# Touchcsreen_PCB.net
KiCad netlist of a schematic drawn in Altium Designer
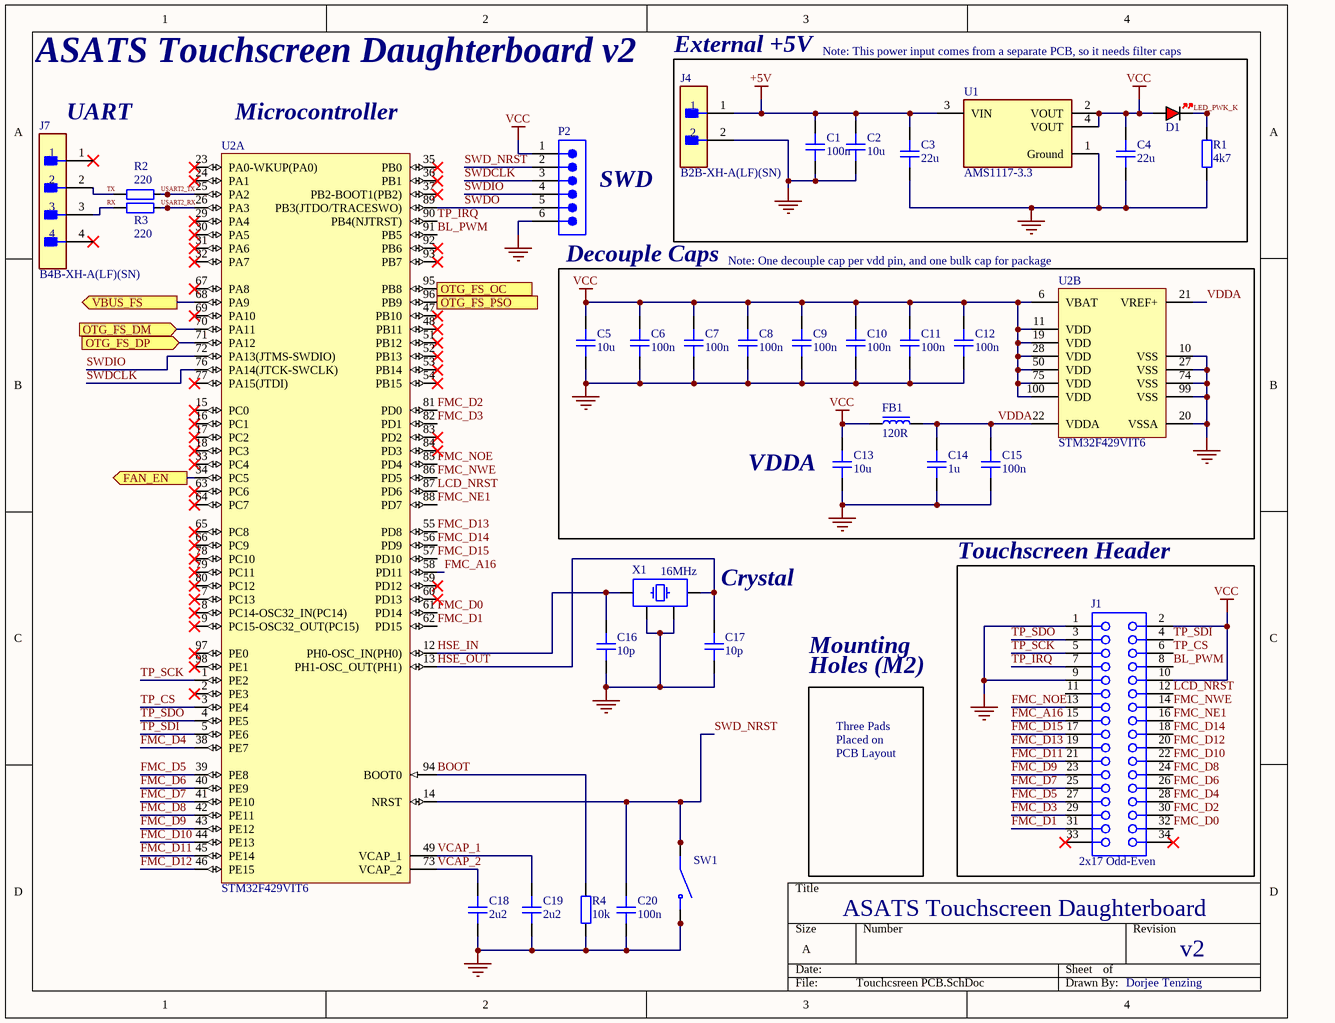
[diagram p0: Touchcsreen PCB.SchDoc]

(export (version "E")
  (design (tool "Eeschema 10.0.6"))
  (components
    (comp (ref "C1")
      (value "100n")
      (footprint "CAP_0402")
      (description "Capacitor SMD 0402")
      (fields
        (field (name "MANUFACTURER") "Samsung Electro-Mechanics")
        (field (name "MANUFACTURER PART NUMBER") "CL05B104KO5NNNC")
      )
      (libsource (lib "Schematic-Lib-PhilsLab") (part "CAP_0402"))
    )
    (comp (ref "C2")
      (value "10u")
      (footprint "CAP_0603")
      (description "Capacitor SMD 0603")
      (fields
        (field (name "MANUFACTURER") "*Samsung Electro-Mechanics")
        (field (name "MANUFACTURER PART NUMBER") "CL10A106MA8NRNC")
      )
      (libsource (lib "Schematic-Lib-PhilsLab") (part "CAP_0603"))
    )
    (comp (ref "C3")
      (value "22u")
      (footprint "CAP_0805")
      (description "Capacitor SMD 0805")
      (fields
        (field (name "MANUFACTURER") "Samsung Electro-Mechanics")
        (field (name "MANUFACTURER PART NUMBER") "CL21A226MAQNNNE")
      )
      (libsource (lib "Schematic-Lib-PhilsLab") (part "CAP_0805"))
    )
    (comp (ref "C4")
      (value "22u")
      (footprint "CAP_0805")
      (description "Capacitor SMD 0805")
      (fields
        (field (name "MANUFACTURER") "Samsung Electro-Mechanics")
        (field (name "MANUFACTURER PART NUMBER") "CL21A226MAQNNNE")
      )
      (libsource (lib "Schematic-Lib-PhilsLab") (part "CAP_0805"))
    )
    (comp (ref "C5")
      (value "10u")
      (footprint "CAP_0603")
      (description "Capacitor SMD 0603")
      (fields
        (field (name "MANUFACTURER") "*Samsung Electro-Mechanics")
        (field (name "MANUFACTURER PART NUMBER") "CL10A106MA8NRNC")
      )
      (libsource (lib "Schematic-Lib-PhilsLab") (part "CAP_0603"))
    )
    (comp (ref "C6")
      (value "100n")
      (footprint "CAP_0402")
      (description "Capacitor SMD 0402")
      (fields
        (field (name "MANUFACTURER") "Samsung Electro-Mechanics")
        (field (name "MANUFACTURER PART NUMBER") "CL05B104KO5NNNC")
      )
      (libsource (lib "Schematic-Lib-PhilsLab") (part "CAP_0402"))
    )
    (comp (ref "C7")
      (value "100n")
      (footprint "CAP_0402")
      (description "Capacitor SMD 0402")
      (fields
        (field (name "MANUFACTURER") "Samsung Electro-Mechanics")
        (field (name "MANUFACTURER PART NUMBER") "CL05B104KO5NNNC")
      )
      (libsource (lib "Schematic-Lib-PhilsLab") (part "CAP_0402"))
    )
    (comp (ref "C8")
      (value "100n")
      (footprint "CAP_0402")
      (description "Capacitor SMD 0402")
      (fields
        (field (name "MANUFACTURER") "Samsung Electro-Mechanics")
        (field (name "MANUFACTURER PART NUMBER") "CL05B104KO5NNNC")
      )
      (libsource (lib "Schematic-Lib-PhilsLab") (part "CAP_0402"))
    )
    (comp (ref "C9")
      (value "100n")
      (footprint "CAP_0402")
      (description "Capacitor SMD 0402")
      (fields
        (field (name "MANUFACTURER") "Samsung Electro-Mechanics")
        (field (name "MANUFACTURER PART NUMBER") "CL05B104KO5NNNC")
      )
      (libsource (lib "Schematic-Lib-PhilsLab") (part "CAP_0402"))
    )
    (comp (ref "C10")
      (value "100n")
      (footprint "CAP_0402")
      (description "Capacitor SMD 0402")
      (fields
        (field (name "MANUFACTURER") "Samsung Electro-Mechanics")
        (field (name "MANUFACTURER PART NUMBER") "CL05B104KO5NNNC")
      )
      (libsource (lib "Schematic-Lib-PhilsLab") (part "CAP_0402"))
    )
    (comp (ref "C11")
      (value "100n")
      (footprint "CAP_0402")
      (description "Capacitor SMD 0402")
      (fields
        (field (name "MANUFACTURER") "Samsung Electro-Mechanics")
        (field (name "MANUFACTURER PART NUMBER") "CL05B104KO5NNNC")
      )
      (libsource (lib "Schematic-Lib-PhilsLab") (part "CAP_0402"))
    )
    (comp (ref "C12")
      (value "100n")
      (footprint "CAP_0402")
      (description "Capacitor SMD 0402")
      (fields
        (field (name "MANUFACTURER") "Samsung Electro-Mechanics")
        (field (name "MANUFACTURER PART NUMBER") "CL05B104KO5NNNC")
      )
      (libsource (lib "Schematic-Lib-PhilsLab") (part "CAP_0402"))
    )
    (comp (ref "C13")
      (value "10u")
      (footprint "CAP_0603")
      (description "Capacitor SMD 0603")
      (fields
        (field (name "MANUFACTURER") "*Samsung Electro-Mechanics")
        (field (name "MANUFACTURER PART NUMBER") "CL10A106MA8NRNC")
      )
      (libsource (lib "Schematic-Lib-PhilsLab") (part "CAP_0603"))
    )
    (comp (ref "C14")
      (value "1u")
      (footprint "CAP_0402")
      (description "Capacitor SMD 0402")
      (fields
        (field (name "MANUFACTURER") "Samsung Electro-Mechanics")
        (field (name "MANUFACTURER PART NUMBER") "CL05A105KA5NQNC")
      )
      (libsource (lib "Schematic-Lib-PhilsLab") (part "CAP_0402"))
    )
    (comp (ref "C15")
      (value "100n")
      (footprint "CAP_0402")
      (description "Capacitor SMD 0402")
      (fields
        (field (name "MANUFACTURER") "Samsung Electro-Mechanics")
        (field (name "MANUFACTURER PART NUMBER") "CL05B104KO5NNNC")
      )
      (libsource (lib "Schematic-Lib-PhilsLab") (part "CAP_0402"))
    )
    (comp (ref "C16")
      (value "10p")
      (footprint "CAP_0402")
      (description "Capacitor SMD 0402")
      (fields
        (field (name "MANUFACTURER") "Samsung Electro-Mechanics")
        (field (name "MANUFACTURER PART NUMBER") "CL05C100JB5NNNC")
      )
      (libsource (lib "Schematic-Lib-PhilsLab") (part "CAP_0402"))
    )
    (comp (ref "C17")
      (value "10p")
      (footprint "CAP_0402")
      (description "Capacitor SMD 0402")
      (fields
        (field (name "MANUFACTURER") "Samsung Electro-Mechanics")
        (field (name "MANUFACTURER PART NUMBER") "CL05C100JB5NNNC")
      )
      (libsource (lib "Schematic-Lib-PhilsLab") (part "CAP_0402"))
    )
    (comp (ref "C18")
      (value "2u2")
      (footprint "CAP_0603")
      (description "Capacitor SMD 0603")
      (fields
        (field (name "MANUFACTURER") "Samsung Electro-Mechanics")
        (field (name "MANUFACTURER PART NUMBER") "CL10A225KO8NNNC")
      )
      (libsource (lib "Schematic-Lib-PhilsLab") (part "CAP_0603"))
    )
    (comp (ref "C19")
      (value "2u2")
      (footprint "CAP_0603")
      (description "Capacitor SMD 0603")
      (fields
        (field (name "MANUFACTURER") "Samsung Electro-Mechanics")
        (field (name "MANUFACTURER PART NUMBER") "CL10A225KO8NNNC")
      )
      (libsource (lib "Schematic-Lib-PhilsLab") (part "CAP_0603"))
    )
    (comp (ref "C20")
      (value "100n")
      (footprint "CAP_0402")
      (description "Capacitor SMD 0402")
      (fields
        (field (name "MANUFACTURER") "Samsung Electro-Mechanics")
        (field (name "MANUFACTURER PART NUMBER") "CL05B104KO5NNNC")
      )
      (libsource (lib "Schematic-Lib-PhilsLab") (part "CAP_0402"))
    )
    (comp (ref "D1")
      (value "RED")
      (footprint "LED_0603_RED")
      (description "LED 0603 RED SMD")
      (fields
        (field (name "MANUFACTURER") "Hubei KENTO Elec")
        (field (name "MANUFACTURER PART NUMBER") "KT-0603R")
      )
      (libsource (lib "Schematic-Lib-PhilsLab") (part "LED_0603_RED"))
    )
    (comp (ref "FB1")
      (value "120R")
      (footprint "FB_0603")
      (description "Ferrite Bead SMD 0603")
      (fields
        (field (name "MANUFACTURER") "Murata Electronics")
        (field (name "MANUFACTURER PART NUMBER") "BLM18PG121SN1D")
      )
      (libsource (lib "Schematic-Lib-PhilsLab") (part "FB_0603"))
    )
    (comp (ref "J1")
      (value "2x17 Odd-Even")
      (footprint "SMTC-SSW-117-01-X-D")
      (description "SQ Post Socket, Through-hole, Vertical, -55 to 105 degC, 2.54 mm Pitch, 34-Pin, Female, RoHS")
      (fields (field (name "PARTNUMBER") "SSW-117-01-T-D") (field (name "MANUFACTURER") "Samtec"))
      (libsource (lib "Altium Content Vault") (part "SMTC-SSW-117-01-X-D"))
    )
    (comp (ref "J4")
      (value "B2B-XH-A(LF)(SN)")
      (footprint "FP-B2B-XH-A_LF_SN-MFG")
      (description "CONN HEADER VERT 2POS 2.5MM")
      (libsource (lib "Altium Content Vault") (part "3bc925449376181038e59eaffc5286c"))
    )
    (comp (ref "J7")
      (value "B4B-XH-A(LF)(SN)")
      (footprint "FP-B4B-XH-A_LF_SN-MFG")
      (description "CONN HEADER VERT 4POS 2.5MM")
      (libsource (lib "Altium Content Vault") (part "299a8cea1bdcbc3624fe62c390fa72c"))
    )
    (comp (ref "P2")
      (value "~")
      (footprint "61300611121")
      (libsource (lib "Altium Content Vault") (part "Header_Male_1R_06P"))
    )
    (comp (ref "R1")
      (value "4k7")
      (footprint "RES_0402")
      (description "Resistor SMD 0402")
      (fields
        (field (name "MANUFACTURER") "UNI-ROYAL(Uniroyal Elec)")
        (field (name "MANUFACTURER PART NUMBER") "0402WGF4701TCE")
      )
      (libsource (lib "Schematic-Lib-PhilsLab") (part "RES_0402"))
    )
    (comp (ref "R2")
      (value "220")
      (footprint "RES_0402")
      (description "Resistor SMD 0402")
      (fields
        (field (name "MANUFACTURER") "UNI-ROYAL(Uniroyal Elec)")
        (field (name "MANUFACTURER PART NUMBER") "0402WGF2200TCE")
      )
      (libsource (lib "Schematic-Lib-PhilsLab") (part "RES_0402"))
    )
    (comp (ref "R3")
      (value "220")
      (footprint "RES_0402")
      (description "Resistor SMD 0402")
      (fields
        (field (name "MANUFACTURER") "UNI-ROYAL(Uniroyal Elec)")
        (field (name "MANUFACTURER PART NUMBER") "0402WGF2200TCE")
      )
      (libsource (lib "Schematic-Lib-PhilsLab") (part "RES_0402"))
    )
    (comp (ref "R4")
      (value "10k")
      (footprint "RES_0402")
      (description "Resistor SMD 0402")
      (fields
        (field (name "MANUFACTURER") "UNI-ROYAL(Uniroyal Elec)")
        (field (name "MANUFACTURER PART NUMBER") "0402WGF1002TCE")
      )
      (libsource (lib "Schematic-Lib-PhilsLab") (part "RES_0402"))
    )
    (comp (ref "SW1")
      (value "~")
      (footprint "SW_TS-1187A-B-A-B")
      (fields
        (field (name "MANUFACTURER") "XKB Connection")
        (field (name "MANUFACTURER PART NUMBER") "TS-1187A-B-A-B")
      )
      (libsource (lib "MySymbols") (part "Push_Button_SW"))
    )
    (comp (ref "U1")
      (value "AMS1117-3.3")
      (footprint "FP-AMS1117-IPC_C")
      (description "LDO Voltage Regulators 1A, 3.3V")
      (fields
        (field (name "OCTOPART") "https://octopart.com/ams1117-3.3-advanced+monolithic+systems-25899300")
        (field (name "MANUFACTURER") "Advanced Monolithic Systems")
      )
      (libsource (lib "Altium Content Vault") (part "8bdbb5f8e77002000e30dd2845d0354"))
    )
    (comp (ref "U2")
      (value "STM32F429VIT6")
      (footprint "STM-LQFP100_N")
      (fields (field (name "MANUFACTURER") "STMicroelectronics"))
      (libsource (lib "Altium Content Vault") (part "MC-ARM-STM32F4X9-SQ100"))
    )
    (comp (ref "X1")
      (value "16MHz")
      (footprint "XTAL_3225")
      (fields
        (field (name "MANUFACTURER") "YXC Crystal Oscillators")
        (field (name "MANUFACTURER PART NUMBER") "X322516MLB4SI")
      )
      (libsource (lib "MySymbols") (part "X3225_16MHZ"))
    )
  )
  (nets
    (net (code "1") (name "+5V") (class "Default")
      (node (ref "C1") (pin "2") (pinfunction "2_2") (pintype "passive"))
      (node (ref "C2") (pin "2") (pinfunction "2_2") (pintype "passive"))
      (node (ref "C3") (pin "2") (pinfunction "2_2") (pintype "passive"))
      (node (ref "J4") (pin "1") (pinfunction "1_1") (pintype "passive"))
      (node (ref "U1") (pin "3") (pinfunction "VIN_3") (pintype "power_in"))
    )
    (net (code "2") (name "/BL_PWM") (class "Default")
      (node (ref "J1") (pin "8") (pinfunction "8_8") (pintype "passive"))
      (node (ref "U2") (pin "91") (pinfunction "PB5_91") (pintype "bidirectional"))
    )
    (net (code "3") (name "/BOOT") (class "Default")
      (node (ref "R4") (pin "2") (pinfunction "2_2") (pintype "passive"))
      (node (ref "U2") (pin "94") (pinfunction "BOOT0_94") (pintype "input"))
    )
    (net (code "4") (name "/FAN_EN") (class "Default")
      (node (ref "U2") (pin "34") (pinfunction "PC5_34") (pintype "bidirectional"))
    )
    (net (code "5") (name "/FMC_A16") (class "Default")
      (node (ref "J1") (pin "15") (pinfunction "15_15") (pintype "passive"))
      (node (ref "U2") (pin "58") (pinfunction "PD11_58") (pintype "bidirectional"))
    )
    (net (code "6") (name "/FMC_D0") (class "Default")
      (node (ref "J1") (pin "32") (pinfunction "32_32") (pintype "passive"))
      (node (ref "U2") (pin "61") (pinfunction "PD14_61") (pintype "bidirectional"))
    )
    (net (code "7") (name "/FMC_D1") (class "Default")
      (node (ref "J1") (pin "31") (pinfunction "31_31") (pintype "passive"))
      (node (ref "U2") (pin "62") (pinfunction "PD15_62") (pintype "bidirectional"))
    )
    (net (code "8") (name "/FMC_D2") (class "Default")
      (node (ref "J1") (pin "30") (pinfunction "30_30") (pintype "passive"))
      (node (ref "U2") (pin "81") (pinfunction "PD0_81") (pintype "bidirectional"))
    )
    (net (code "9") (name "/FMC_D3") (class "Default")
      (node (ref "J1") (pin "29") (pinfunction "29_29") (pintype "passive"))
      (node (ref "U2") (pin "82") (pinfunction "PD1_82") (pintype "bidirectional"))
    )
    (net (code "10") (name "/FMC_D4") (class "Default")
      (node (ref "J1") (pin "28") (pinfunction "28_28") (pintype "passive"))
      (node (ref "U2") (pin "38") (pinfunction "PE7_38") (pintype "bidirectional"))
    )
    (net (code "11") (name "/FMC_D5") (class "Default")
      (node (ref "J1") (pin "27") (pinfunction "27_27") (pintype "passive"))
      (node (ref "U2") (pin "39") (pinfunction "PE8_39") (pintype "bidirectional"))
    )
    (net (code "12") (name "/FMC_D6") (class "Default")
      (node (ref "J1") (pin "26") (pinfunction "26_26") (pintype "passive"))
      (node (ref "U2") (pin "40") (pinfunction "PE9_40") (pintype "bidirectional"))
    )
    (net (code "13") (name "/FMC_D7") (class "Default")
      (node (ref "J1") (pin "25") (pinfunction "25_25") (pintype "passive"))
      (node (ref "U2") (pin "41") (pinfunction "PE10_41") (pintype "bidirectional"))
    )
    (net (code "14") (name "/FMC_D8") (class "Default")
      (node (ref "J1") (pin "24") (pinfunction "24_24") (pintype "passive"))
      (node (ref "U2") (pin "42") (pinfunction "PE11_42") (pintype "bidirectional"))
    )
    (net (code "15") (name "/FMC_D9") (class "Default")
      (node (ref "J1") (pin "23") (pinfunction "23_23") (pintype "passive"))
      (node (ref "U2") (pin "43") (pinfunction "PE12_43") (pintype "bidirectional"))
    )
    (net (code "16") (name "/FMC_D10") (class "Default")
      (node (ref "J1") (pin "22") (pinfunction "22_22") (pintype "passive"))
      (node (ref "U2") (pin "44") (pinfunction "PE13_44") (pintype "bidirectional"))
    )
    (net (code "17") (name "/FMC_D11") (class "Default")
      (node (ref "J1") (pin "21") (pinfunction "21_21") (pintype "passive"))
      (node (ref "U2") (pin "45") (pinfunction "PE14_45") (pintype "bidirectional"))
    )
    (net (code "18") (name "/FMC_D12") (class "Default")
      (node (ref "J1") (pin "20") (pinfunction "20_20") (pintype "passive"))
      (node (ref "U2") (pin "46") (pinfunction "PE15_46") (pintype "bidirectional"))
    )
    (net (code "19") (name "/FMC_D13") (class "Default")
      (node (ref "J1") (pin "19") (pinfunction "19_19") (pintype "passive"))
      (node (ref "U2") (pin "55") (pinfunction "PD8_55") (pintype "bidirectional"))
    )
    (net (code "20") (name "/FMC_D14") (class "Default")
      (node (ref "J1") (pin "18") (pinfunction "18_18") (pintype "passive"))
      (node (ref "U2") (pin "56") (pinfunction "PD9_56") (pintype "bidirectional"))
    )
    (net (code "21") (name "/FMC_D15") (class "Default")
      (node (ref "J1") (pin "17") (pinfunction "17_17") (pintype "passive"))
      (node (ref "U2") (pin "57") (pinfunction "PD10_57") (pintype "bidirectional"))
    )
    (net (code "22") (name "/FMC_NE1") (class "Default")
      (node (ref "J1") (pin "16") (pinfunction "16_16") (pintype "passive"))
      (node (ref "U2") (pin "88") (pinfunction "PD7_88") (pintype "bidirectional"))
    )
    (net (code "23") (name "/FMC_NOE") (class "Default")
      (node (ref "J1") (pin "13") (pinfunction "13_13") (pintype "passive"))
      (node (ref "U2") (pin "85") (pinfunction "PD4_85") (pintype "bidirectional"))
    )
    (net (code "24") (name "/FMC_NWE") (class "Default")
      (node (ref "J1") (pin "14") (pinfunction "14_14") (pintype "passive"))
      (node (ref "U2") (pin "86") (pinfunction "PD5_86") (pintype "bidirectional"))
    )
    (net (code "25") (name "/HSE_IN") (class "Default")
      (node (ref "C16") (pin "2") (pinfunction "2_2") (pintype "passive"))
      (node (ref "U2") (pin "12") (pinfunction "PH0-OSC_IN(PH0)_12") (pintype "bidirectional"))
      (node (ref "X1") (pin "1") (pinfunction "1_1") (pintype "passive"))
    )
    (net (code "26") (name "/HSE_OUT") (class "Default")
      (node (ref "C17") (pin "2") (pinfunction "2_2") (pintype "passive"))
      (node (ref "U2") (pin "13") (pinfunction "PH1-OSC_OUT(PH1)_13") (pintype "bidirectional"))
      (node (ref "X1") (pin "3") (pinfunction "3_3") (pintype "passive"))
    )
    (net (code "27") (name "/LCD_NRST") (class "Default")
      (node (ref "J1") (pin "12") (pinfunction "12_12") (pintype "passive"))
      (node (ref "U2") (pin "87") (pinfunction "PD6_87") (pintype "bidirectional"))
    )
    (net (code "28") (name "/LED_PWK_K") (class "Default")
      (node (ref "D1") (pin "K") (pinfunction "K_K") (pintype "passive"))
      (node (ref "R1") (pin "2") (pinfunction "2_2") (pintype "passive"))
    )
    (net (code "29") (name "/OTG_FS_DM") (class "Default")
      (node (ref "U2") (pin "70") (pinfunction "PA11_70") (pintype "bidirectional"))
    )
    (net (code "30") (name "/OTG_FS_DP") (class "Default")
      (node (ref "U2") (pin "71") (pinfunction "PA12_71") (pintype "bidirectional"))
    )
    (net (code "31") (name "/OTG_FS_OC") (class "Default")
      (node (ref "U2") (pin "95") (pinfunction "PB8_95") (pintype "bidirectional"))
    )
    (net (code "32") (name "/OTG_FS_PSO") (class "Default")
      (node (ref "U2") (pin "96") (pinfunction "PB9_96") (pintype "bidirectional"))
    )
    (net (code "33") (name "/RX") (class "Default")
      (node (ref "J7") (pin "3") (pinfunction "3_3") (pintype "passive"))
      (node (ref "R3") (pin "1") (pinfunction "1_1") (pintype "passive"))
    )
    (net (code "34") (name "/SWDCLK") (class "Default")
      (node (ref "P2") (pin "3") (pinfunction "3_3") (pintype "passive"))
      (node (ref "U2") (pin "76") (pinfunction "PA14(JTCK-SWCLK)_76") (pintype "bidirectional"))
    )
    (net (code "35") (name "/SWDIO") (class "Default")
      (node (ref "P2") (pin "4") (pinfunction "4_4") (pintype "passive"))
      (node (ref "U2") (pin "72") (pinfunction "PA13(JTMS-SWDIO)_72") (pintype "bidirectional"))
    )
    (net (code "36") (name "/SWDO") (class "Default")
      (node (ref "P2") (pin "5") (pinfunction "5_5") (pintype "passive"))
      (node (ref "U2") (pin "89") (pinfunction "PB3(JTDO/TRACESWO)_89") (pintype "bidirectional"))
    )
    (net (code "37") (name "/SWD_NRST") (class "Default")
      (node (ref "C20") (pin "2") (pinfunction "2_2") (pintype "passive"))
      (node (ref "P2") (pin "2") (pinfunction "2_2") (pintype "passive"))
      (node (ref "SW1") (pin "A") (pinfunction "COM_A") (pintype "passive"))
      (node (ref "SW1") (pin "B") (pinfunction "COM_B") (pintype "passive"))
      (node (ref "U2") (pin "14") (pinfunction "NRST_14") (pintype "bidirectional"))
    )
    (net (code "38") (name "/TP_CS") (class "Default")
      (node (ref "J1") (pin "6") (pinfunction "6_6") (pintype "passive"))
      (node (ref "U2") (pin "3") (pinfunction "PE4_3") (pintype "bidirectional"))
    )
    (net (code "39") (name "/TP_IRQ") (class "Default")
      (node (ref "J1") (pin "7") (pinfunction "7_7") (pintype "passive"))
      (node (ref "U2") (pin "90") (pinfunction "PB4(NJTRST)_90") (pintype "bidirectional"))
    )
    (net (code "40") (name "/TP_SCK") (class "Default")
      (node (ref "J1") (pin "5") (pinfunction "5_5") (pintype "passive"))
      (node (ref "U2") (pin "1") (pinfunction "PE2_1") (pintype "bidirectional"))
    )
    (net (code "41") (name "/TP_SDI") (class "Default")
      (node (ref "J1") (pin "4") (pinfunction "4_4") (pintype "passive"))
      (node (ref "U2") (pin "5") (pinfunction "PE6_5") (pintype "bidirectional"))
    )
    (net (code "42") (name "/TP_SDO") (class "Default")
      (node (ref "J1") (pin "3") (pinfunction "3_3") (pintype "passive"))
      (node (ref "U2") (pin "4") (pinfunction "PE5_4") (pintype "bidirectional"))
    )
    (net (code "43") (name "/TX") (class "Default")
      (node (ref "J7") (pin "2") (pinfunction "2_2") (pintype "passive"))
      (node (ref "R2") (pin "1") (pinfunction "1_1") (pintype "passive"))
    )
    (net (code "44") (name "/USART2_RX") (class "Default")
      (node (ref "R3") (pin "2") (pinfunction "2_2") (pintype "passive"))
      (node (ref "U2") (pin "26") (pinfunction "PA3_26") (pintype "bidirectional"))
    )
    (net (code "45") (name "/USART2_TX") (class "Default")
      (node (ref "R2") (pin "2") (pinfunction "2_2") (pintype "passive"))
      (node (ref "U2") (pin "25") (pinfunction "PA2_25") (pintype "bidirectional"))
    )
    (net (code "46") (name "/VBUS_FS") (class "Default")
      (node (ref "U2") (pin "68") (pinfunction "PA9_68") (pintype "bidirectional"))
    )
    (net (code "47") (name "/VCAP_1") (class "Default")
      (node (ref "C19") (pin "2") (pinfunction "2_2") (pintype "passive"))
      (node (ref "U2") (pin "49") (pinfunction "VCAP_1_49") (pintype "power_in"))
    )
    (net (code "48") (name "/VCAP_2") (class "Default")
      (node (ref "C18") (pin "2") (pinfunction "2_2") (pintype "passive"))
      (node (ref "U2") (pin "73") (pinfunction "VCAP_2_73") (pintype "power_in"))
    )
    (net (code "49") (name "/VDDA") (class "Default")
      (node (ref "C14") (pin "1") (pinfunction "1_1") (pintype "passive"))
      (node (ref "C15") (pin "2") (pinfunction "2_2") (pintype "passive"))
      (node (ref "FB1") (pin "2") (pinfunction "2_2") (pintype "passive"))
      (node (ref "U2") (pin "21") (pinfunction "VREF+_21") (pintype "power_in"))
      (node (ref "U2") (pin "22") (pinfunction "VDDA_22") (pintype "power_in"))
    )
    (net (code "50") (name "GND") (class "Default")
      (node (ref "C1") (pin "1") (pinfunction "1_1") (pintype "passive"))
      (node (ref "C10") (pin "1") (pinfunction "1_1") (pintype "passive"))
      (node (ref "C11") (pin "1") (pinfunction "1_1") (pintype "passive"))
      (node (ref "C12") (pin "1") (pinfunction "1_1") (pintype "passive"))
      (node (ref "C13") (pin "1") (pinfunction "1_1") (pintype "passive"))
      (node (ref "C14") (pin "2") (pinfunction "2_2") (pintype "passive"))
      (node (ref "C15") (pin "1") (pinfunction "1_1") (pintype "passive"))
      (node (ref "C16") (pin "1") (pinfunction "1_1") (pintype "passive"))
      (node (ref "C17") (pin "1") (pinfunction "1_1") (pintype "passive"))
      (node (ref "C18") (pin "1") (pinfunction "1_1") (pintype "passive"))
      (node (ref "C19") (pin "1") (pinfunction "1_1") (pintype "passive"))
      (node (ref "C2") (pin "1") (pinfunction "1_1") (pintype "passive"))
      (node (ref "C20") (pin "1") (pinfunction "1_1") (pintype "passive"))
      (node (ref "C3") (pin "1") (pinfunction "1_1") (pintype "passive"))
      (node (ref "C4") (pin "1") (pinfunction "1_1") (pintype "passive"))
      (node (ref "C5") (pin "1") (pinfunction "1_1") (pintype "passive"))
      (node (ref "C6") (pin "1") (pinfunction "1_1") (pintype "passive"))
      (node (ref "C7") (pin "1") (pinfunction "1_1") (pintype "passive"))
      (node (ref "C8") (pin "1") (pinfunction "1_1") (pintype "passive"))
      (node (ref "C9") (pin "1") (pinfunction "1_1") (pintype "passive"))
      (node (ref "J1") (pin "1") (pinfunction "1_1") (pintype "passive"))
      (node (ref "J1") (pin "9") (pinfunction "9_9") (pintype "passive"))
      (node (ref "J4") (pin "2") (pinfunction "2_2") (pintype "passive"))
      (node (ref "P2") (pin "6") (pinfunction "6_6") (pintype "passive"))
      (node (ref "R1") (pin "1") (pinfunction "1_1") (pintype "passive"))
      (node (ref "R4") (pin "1") (pinfunction "1_1") (pintype "passive"))
      (node (ref "SW1") (pin "C") (pinfunction "NO_C") (pintype "passive"))
      (node (ref "SW1") (pin "D") (pinfunction "NO_D") (pintype "passive"))
      (node (ref "U1") (pin "1") (pinfunction "Ground_1") (pintype "power_in"))
      (node (ref "U2") (pin "10") (pinfunction "VSS_10") (pintype "power_in"))
      (node (ref "U2") (pin "20") (pinfunction "VSSA_20") (pintype "power_in"))
      (node (ref "U2") (pin "27") (pinfunction "VSS_27") (pintype "power_in"))
      (node (ref "U2") (pin "74") (pinfunction "VSS_74") (pintype "power_in"))
      (node (ref "U2") (pin "99") (pinfunction "VSS_99") (pintype "power_in"))
      (node (ref "X1") (pin "2") (pinfunction "2_2") (pintype "passive"))
      (node (ref "X1") (pin "4") (pinfunction "4_4") (pintype "passive"))
    )
    (net (code "51") (name "VCC") (class "Default")
      (node (ref "C10") (pin "2") (pinfunction "2_2") (pintype "passive"))
      (node (ref "C11") (pin "2") (pinfunction "2_2") (pintype "passive"))
      (node (ref "C12") (pin "2") (pinfunction "2_2") (pintype "passive"))
      (node (ref "C13") (pin "2") (pinfunction "2_2") (pintype "passive"))
      (node (ref "C4") (pin "2") (pinfunction "2_2") (pintype "passive"))
      (node (ref "C5") (pin "2") (pinfunction "2_2") (pintype "passive"))
      (node (ref "C6") (pin "2") (pinfunction "2_2") (pintype "passive"))
      (node (ref "C7") (pin "2") (pinfunction "2_2") (pintype "passive"))
      (node (ref "C8") (pin "2") (pinfunction "2_2") (pintype "passive"))
      (node (ref "C9") (pin "2") (pinfunction "2_2") (pintype "passive"))
      (node (ref "D1") (pin "A") (pinfunction "A_A") (pintype "passive"))
      (node (ref "FB1") (pin "1") (pinfunction "1_1") (pintype "passive"))
      (node (ref "J1") (pin "10") (pinfunction "10_10") (pintype "passive"))
      (node (ref "J1") (pin "2") (pinfunction "2_2") (pintype "passive"))
      (node (ref "P2") (pin "1") (pinfunction "1_1") (pintype "passive"))
      (node (ref "U1") (pin "2") (pinfunction "VOUT_2") (pintype "passive"))
      (node (ref "U1") (pin "4") (pinfunction "VOUT_4") (pintype "passive"))
      (node (ref "U2") (pin "100") (pinfunction "VDD_100") (pintype "power_in"))
      (node (ref "U2") (pin "11") (pinfunction "VDD_11") (pintype "power_in"))
      (node (ref "U2") (pin "19") (pinfunction "VDD_19") (pintype "power_in"))
      (node (ref "U2") (pin "28") (pinfunction "VDD_28") (pintype "power_in"))
      (node (ref "U2") (pin "50") (pinfunction "VDD_50") (pintype "power_in"))
      (node (ref "U2") (pin "6") (pinfunction "VBAT_6") (pintype "power_in"))
      (node (ref "U2") (pin "75") (pinfunction "VDD_75") (pintype "power_in"))
    )
    (net (code "52") (name "unconnected-(J1-Pad11)") (class "Default")
      (node (ref "J1") (pin "11") (pinfunction "11_11") (pintype "passive"))
    )
    (net (code "53") (name "unconnected-(J1-Pad33)") (class "Default")
      (node (ref "J1") (pin "33") (pinfunction "33_33") (pintype "passive+no_connect"))
    )
    (net (code "54") (name "unconnected-(J1-Pad34)") (class "Default")
      (node (ref "J1") (pin "34") (pinfunction "34_34") (pintype "passive+no_connect"))
    )
    (net (code "55") (name "unconnected-(J7-Pad1)") (class "Default")
      (node (ref "J7") (pin "1") (pinfunction "1_1") (pintype "passive+no_connect"))
    )
    (net (code "56") (name "unconnected-(J7-Pad4)") (class "Default")
      (node (ref "J7") (pin "4") (pinfunction "4_4") (pintype "passive+no_connect"))
    )
    (net (code "57") (name "unconnected-(U2A-PA0-WKUP(PA0)-Pad23)") (class "Default")
      (node (ref "U2") (pin "23") (pinfunction "PA0-WKUP(PA0)_23") (pintype "bidirectional+no_connect"))
    )
    (net (code "58") (name "unconnected-(U2A-PA1-Pad24)") (class "Default")
      (node (ref "U2") (pin "24") (pinfunction "PA1_24") (pintype "bidirectional+no_connect"))
    )
    (net (code "59") (name "unconnected-(U2A-PA4-Pad29)") (class "Default")
      (node (ref "U2") (pin "29") (pinfunction "PA4_29") (pintype "bidirectional+no_connect"))
    )
    (net (code "60") (name "unconnected-(U2A-PA5-Pad30)") (class "Default")
      (node (ref "U2") (pin "30") (pinfunction "PA5_30") (pintype "bidirectional+no_connect"))
    )
    (net (code "61") (name "unconnected-(U2A-PA6-Pad31)") (class "Default")
      (node (ref "U2") (pin "31") (pinfunction "PA6_31") (pintype "bidirectional+no_connect"))
    )
    (net (code "62") (name "unconnected-(U2A-PA7-Pad32)") (class "Default")
      (node (ref "U2") (pin "32") (pinfunction "PA7_32") (pintype "bidirectional+no_connect"))
    )
    (net (code "63") (name "unconnected-(U2A-PA8-Pad67)") (class "Default")
      (node (ref "U2") (pin "67") (pinfunction "PA8_67") (pintype "bidirectional+no_connect"))
    )
    (net (code "64") (name "unconnected-(U2A-PA10-Pad69)") (class "Default")
      (node (ref "U2") (pin "69") (pinfunction "PA10_69") (pintype "bidirectional+no_connect"))
    )
    (net (code "65") (name "unconnected-(U2A-PA15(JTDI)-Pad77)") (class "Default")
      (node (ref "U2") (pin "77") (pinfunction "PA15(JTDI)_77") (pintype "bidirectional+no_connect"))
    )
    (net (code "66") (name "unconnected-(U2A-PB0-Pad35)") (class "Default")
      (node (ref "U2") (pin "35") (pinfunction "PB0_35") (pintype "bidirectional+no_connect"))
    )
    (net (code "67") (name "unconnected-(U2A-PB1-Pad36)") (class "Default")
      (node (ref "U2") (pin "36") (pinfunction "PB1_36") (pintype "bidirectional+no_connect"))
    )
    (net (code "68") (name "unconnected-(U2A-PB2-BOOT1(PB2)-Pad37)") (class "Default")
      (node (ref "U2") (pin "37") (pinfunction "PB2-BOOT1(PB2)_37") (pintype "bidirectional+no_connect"))
    )
    (net (code "69") (name "unconnected-(U2A-PB6-Pad92)") (class "Default")
      (node (ref "U2") (pin "92") (pinfunction "PB6_92") (pintype "bidirectional+no_connect"))
    )
    (net (code "70") (name "unconnected-(U2A-PB7-Pad93)") (class "Default")
      (node (ref "U2") (pin "93") (pinfunction "PB7_93") (pintype "bidirectional+no_connect"))
    )
    (net (code "71") (name "unconnected-(U2A-PB10-Pad47)") (class "Default")
      (node (ref "U2") (pin "47") (pinfunction "PB10_47") (pintype "bidirectional+no_connect"))
    )
    (net (code "72") (name "unconnected-(U2A-PB11-Pad48)") (class "Default")
      (node (ref "U2") (pin "48") (pinfunction "PB11_48") (pintype "bidirectional+no_connect"))
    )
    (net (code "73") (name "unconnected-(U2A-PB12-Pad51)") (class "Default")
      (node (ref "U2") (pin "51") (pinfunction "PB12_51") (pintype "bidirectional+no_connect"))
    )
    (net (code "74") (name "unconnected-(U2A-PB13-Pad52)") (class "Default")
      (node (ref "U2") (pin "52") (pinfunction "PB13_52") (pintype "bidirectional+no_connect"))
    )
    (net (code "75") (name "unconnected-(U2A-PB14-Pad53)") (class "Default")
      (node (ref "U2") (pin "53") (pinfunction "PB14_53") (pintype "bidirectional+no_connect"))
    )
    (net (code "76") (name "unconnected-(U2A-PB15-Pad54)") (class "Default")
      (node (ref "U2") (pin "54") (pinfunction "PB15_54") (pintype "bidirectional+no_connect"))
    )
    (net (code "77") (name "unconnected-(U2A-PC0-Pad15)") (class "Default")
      (node (ref "U2") (pin "15") (pinfunction "PC0_15") (pintype "bidirectional+no_connect"))
    )
    (net (code "78") (name "unconnected-(U2A-PC1-Pad16)") (class "Default")
      (node (ref "U2") (pin "16") (pinfunction "PC1_16") (pintype "bidirectional+no_connect"))
    )
    (net (code "79") (name "unconnected-(U2A-PC2-Pad17)") (class "Default")
      (node (ref "U2") (pin "17") (pinfunction "PC2_17") (pintype "bidirectional+no_connect"))
    )
    (net (code "80") (name "unconnected-(U2A-PC3-Pad18)") (class "Default")
      (node (ref "U2") (pin "18") (pinfunction "PC3_18") (pintype "bidirectional+no_connect"))
    )
    (net (code "81") (name "unconnected-(U2A-PC4-Pad33)") (class "Default")
      (node (ref "U2") (pin "33") (pinfunction "PC4_33") (pintype "bidirectional+no_connect"))
    )
    (net (code "82") (name "unconnected-(U2A-PC6-Pad63)") (class "Default")
      (node (ref "U2") (pin "63") (pinfunction "PC6_63") (pintype "bidirectional+no_connect"))
    )
    (net (code "83") (name "unconnected-(U2A-PC7-Pad64)") (class "Default")
      (node (ref "U2") (pin "64") (pinfunction "PC7_64") (pintype "bidirectional+no_connect"))
    )
    (net (code "84") (name "unconnected-(U2A-PC8-Pad65)") (class "Default")
      (node (ref "U2") (pin "65") (pinfunction "PC8_65") (pintype "bidirectional+no_connect"))
    )
    (net (code "85") (name "unconnected-(U2A-PC9-Pad66)") (class "Default")
      (node (ref "U2") (pin "66") (pinfunction "PC9_66") (pintype "bidirectional+no_connect"))
    )
    (net (code "86") (name "unconnected-(U2A-PC10-Pad78)") (class "Default")
      (node (ref "U2") (pin "78") (pinfunction "PC10_78") (pintype "bidirectional+no_connect"))
    )
    (net (code "87") (name "unconnected-(U2A-PC11-Pad79)") (class "Default")
      (node (ref "U2") (pin "79") (pinfunction "PC11_79") (pintype "bidirectional+no_connect"))
    )
    (net (code "88") (name "unconnected-(U2A-PC12-Pad80)") (class "Default")
      (node (ref "U2") (pin "80") (pinfunction "PC12_80") (pintype "bidirectional+no_connect"))
    )
    (net (code "89") (name "unconnected-(U2A-PC13-Pad7)") (class "Default")
      (node (ref "U2") (pin "7") (pinfunction "PC13_7") (pintype "bidirectional+no_connect"))
    )
    (net (code "90") (name "unconnected-(U2A-PC14-OSC32_IN(PC14)-Pad8)") (class "Default")
      (node (ref "U2") (pin "8") (pinfunction "PC14-OSC32_IN(PC14)_8") (pintype "bidirectional+no_connect"))
    )
    (net (code "91") (name "unconnected-(U2A-PC15-OSC32_OUT(PC15)-Pad9)") (class "Default")
      (node (ref "U2") (pin "9") (pinfunction "PC15-OSC32_OUT(PC15)_9") (pintype "bidirectional+no_connect"))
    )
    (net (code "92") (name "unconnected-(U2A-PD2-Pad83)") (class "Default")
      (node (ref "U2") (pin "83") (pinfunction "PD2_83") (pintype "bidirectional+no_connect"))
    )
    (net (code "93") (name "unconnected-(U2A-PD3-Pad84)") (class "Default")
      (node (ref "U2") (pin "84") (pinfunction "PD3_84") (pintype "bidirectional+no_connect"))
    )
    (net (code "94") (name "unconnected-(U2A-PD12-Pad59)") (class "Default")
      (node (ref "U2") (pin "59") (pinfunction "PD12_59") (pintype "bidirectional+no_connect"))
    )
    (net (code "95") (name "unconnected-(U2A-PD13-Pad60)") (class "Default")
      (node (ref "U2") (pin "60") (pinfunction "PD13_60") (pintype "bidirectional+no_connect"))
    )
    (net (code "96") (name "unconnected-(U2A-PE0-Pad97)") (class "Default")
      (node (ref "U2") (pin "97") (pinfunction "PE0_97") (pintype "bidirectional+no_connect"))
    )
    (net (code "97") (name "unconnected-(U2A-PE1-Pad98)") (class "Default")
      (node (ref "U2") (pin "98") (pinfunction "PE1_98") (pintype "bidirectional+no_connect"))
    )
    (net (code "98") (name "unconnected-(U2A-PE3-Pad2)") (class "Default")
      (node (ref "U2") (pin "2") (pinfunction "PE3_2") (pintype "bidirectional+no_connect"))
    )
  )
)
